# fram.net
KiCad netlist of a schematic drawn in Altium Designer
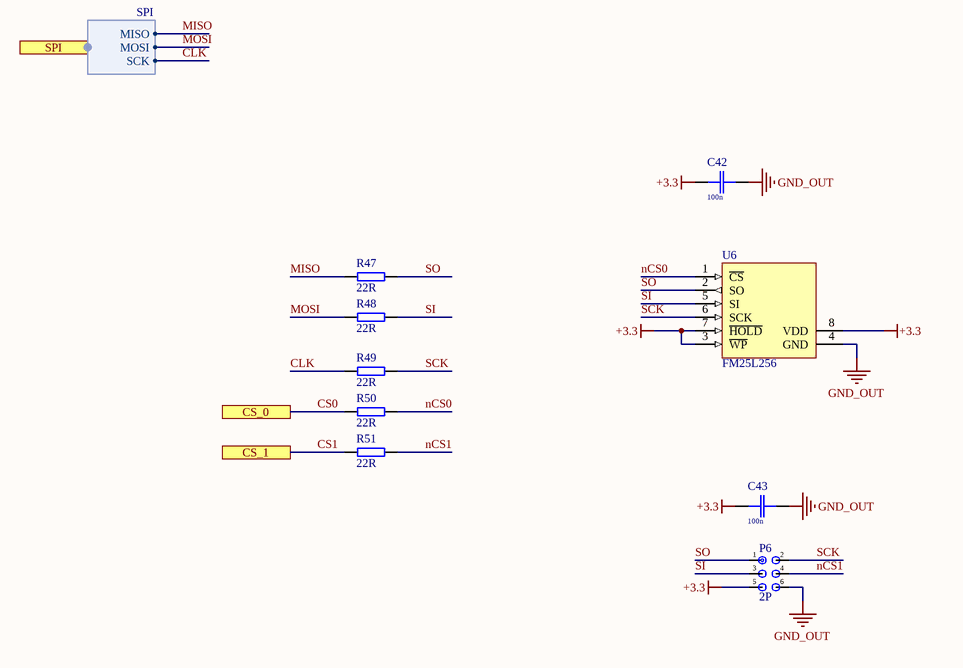
[diagram p0: fram.SchDoc]

(export (version "E")
  (design (tool "Eeschema 10.0.6"))
  (components
    (comp (ref "C42")
      (value "100n")
      (footprint "C0603")
      (description "SMD-0603")
      (libsource (lib "SMD-RCL") (part "C-0603"))
    )
    (comp (ref "C43")
      (value "100n")
      (footprint "C0603")
      (description "SMD-0603")
      (libsource (lib "SMD-RCL") (part "C-0603"))
    )
    (comp (ref "P6") (value "2P") (footprint "CON: PLS-6") (libsource (lib "CONNECTOR") (part "PLS_PBD_6")))
    (comp (ref "R47") (value "22R") (footprint "RES: 0603") (libsource (lib "PASSIVE") (part "R_SMD")))
    (comp (ref "R48") (value "22R") (footprint "RES: 0603") (libsource (lib "PASSIVE") (part "R_SMD")))
    (comp (ref "R49") (value "22R") (footprint "RES: 0603") (libsource (lib "PASSIVE") (part "R_SMD")))
    (comp (ref "R50") (value "22R") (footprint "RES: 0603") (libsource (lib "PASSIVE") (part "R_SMD")))
    (comp (ref "R51") (value "22R") (footprint "RES: 0603") (libsource (lib "PASSIVE") (part "R_SMD")))
    (comp (ref "U6")
      (value "FM25L256")
      (footprint "SOIC127P600X175-8M")
      (libsource (lib "Main") (part "FM25L256"))
    )
  )
  (nets
    (net (code "2") (name "+3.3") (class "Default")
      (node (ref "C42") (pin "1") (pinfunction "1_1") (pintype "passive"))
      (node (ref "C43") (pin "1") (pinfunction "1_1") (pintype "passive"))
      (node (ref "P6") (pin "5") (pinfunction "5_5") (pintype "passive"))
      (node (ref "U6") (pin "3") (pinfunction "~{WP}_3") (pintype "input"))
      (node (ref "U6") (pin "7") (pinfunction "~{HOLD}_7") (pintype "input"))
      (node (ref "U6") (pin "8") (pinfunction "VDD_8") (pintype "power_in"))
    )
    (net (code "3") (name "/CLK") (class "Default")
      (node (ref "R49") (pin "2") (pinfunction "2_2") (pintype "passive"))
    )
    (net (code "4") (name "/CS0") (class "Default")
      (node (ref "R50") (pin "2") (pinfunction "2_2") (pintype "passive"))
    )
    (net (code "5") (name "/CS1") (class "Default")
      (node (ref "R51") (pin "2") (pinfunction "2_2") (pintype "passive"))
    )
    (net (code "6") (name "/MISO") (class "Default")
      (node (ref "R47") (pin "2") (pinfunction "2_2") (pintype "passive"))
    )
    (net (code "7") (name "/MOSI") (class "Default")
      (node (ref "R48") (pin "2") (pinfunction "2_2") (pintype "passive"))
    )
    (net (code "8") (name "/SCK") (class "Default")
      (node (ref "P6") (pin "2") (pinfunction "2_2") (pintype "passive"))
      (node (ref "R49") (pin "1") (pinfunction "1_1") (pintype "passive"))
      (node (ref "U6") (pin "6") (pinfunction "SCK_6") (pintype "input"))
    )
    (net (code "9") (name "/SI") (class "Default")
      (node (ref "P6") (pin "3") (pinfunction "3_3") (pintype "passive"))
      (node (ref "R48") (pin "1") (pinfunction "1_1") (pintype "passive"))
      (node (ref "U6") (pin "5") (pinfunction "SI_5") (pintype "input"))
    )
    (net (code "10") (name "/SO") (class "Default")
      (node (ref "P6") (pin "1") (pinfunction "1_1") (pintype "passive"))
      (node (ref "R47") (pin "1") (pinfunction "1_1") (pintype "passive"))
      (node (ref "U6") (pin "2") (pinfunction "SO_2") (pintype "output"))
    )
    (net (code "11") (name "/nCS0") (class "Default")
      (node (ref "R50") (pin "1") (pinfunction "1_1") (pintype "passive"))
      (node (ref "U6") (pin "1") (pinfunction "~{CS}_1") (pintype "input"))
    )
    (net (code "12") (name "/nCS1") (class "Default")
      (node (ref "P6") (pin "4") (pinfunction "4_4") (pintype "passive"))
      (node (ref "R51") (pin "1") (pinfunction "1_1") (pintype "passive"))
    )
    (net (code "14") (name "GND_OUT") (class "Default")
      (node (ref "C42") (pin "2") (pinfunction "2_2") (pintype "passive"))
      (node (ref "C43") (pin "2") (pinfunction "2_2") (pintype "passive"))
      (node (ref "P6") (pin "6") (pinfunction "6_6") (pintype "passive"))
      (node (ref "U6") (pin "4") (pinfunction "GND_4") (pintype "power_in"))
    )
  )
)
